# queso_dip_v4_8.net
KiCad netlist of a schematic drawn in EAGLE
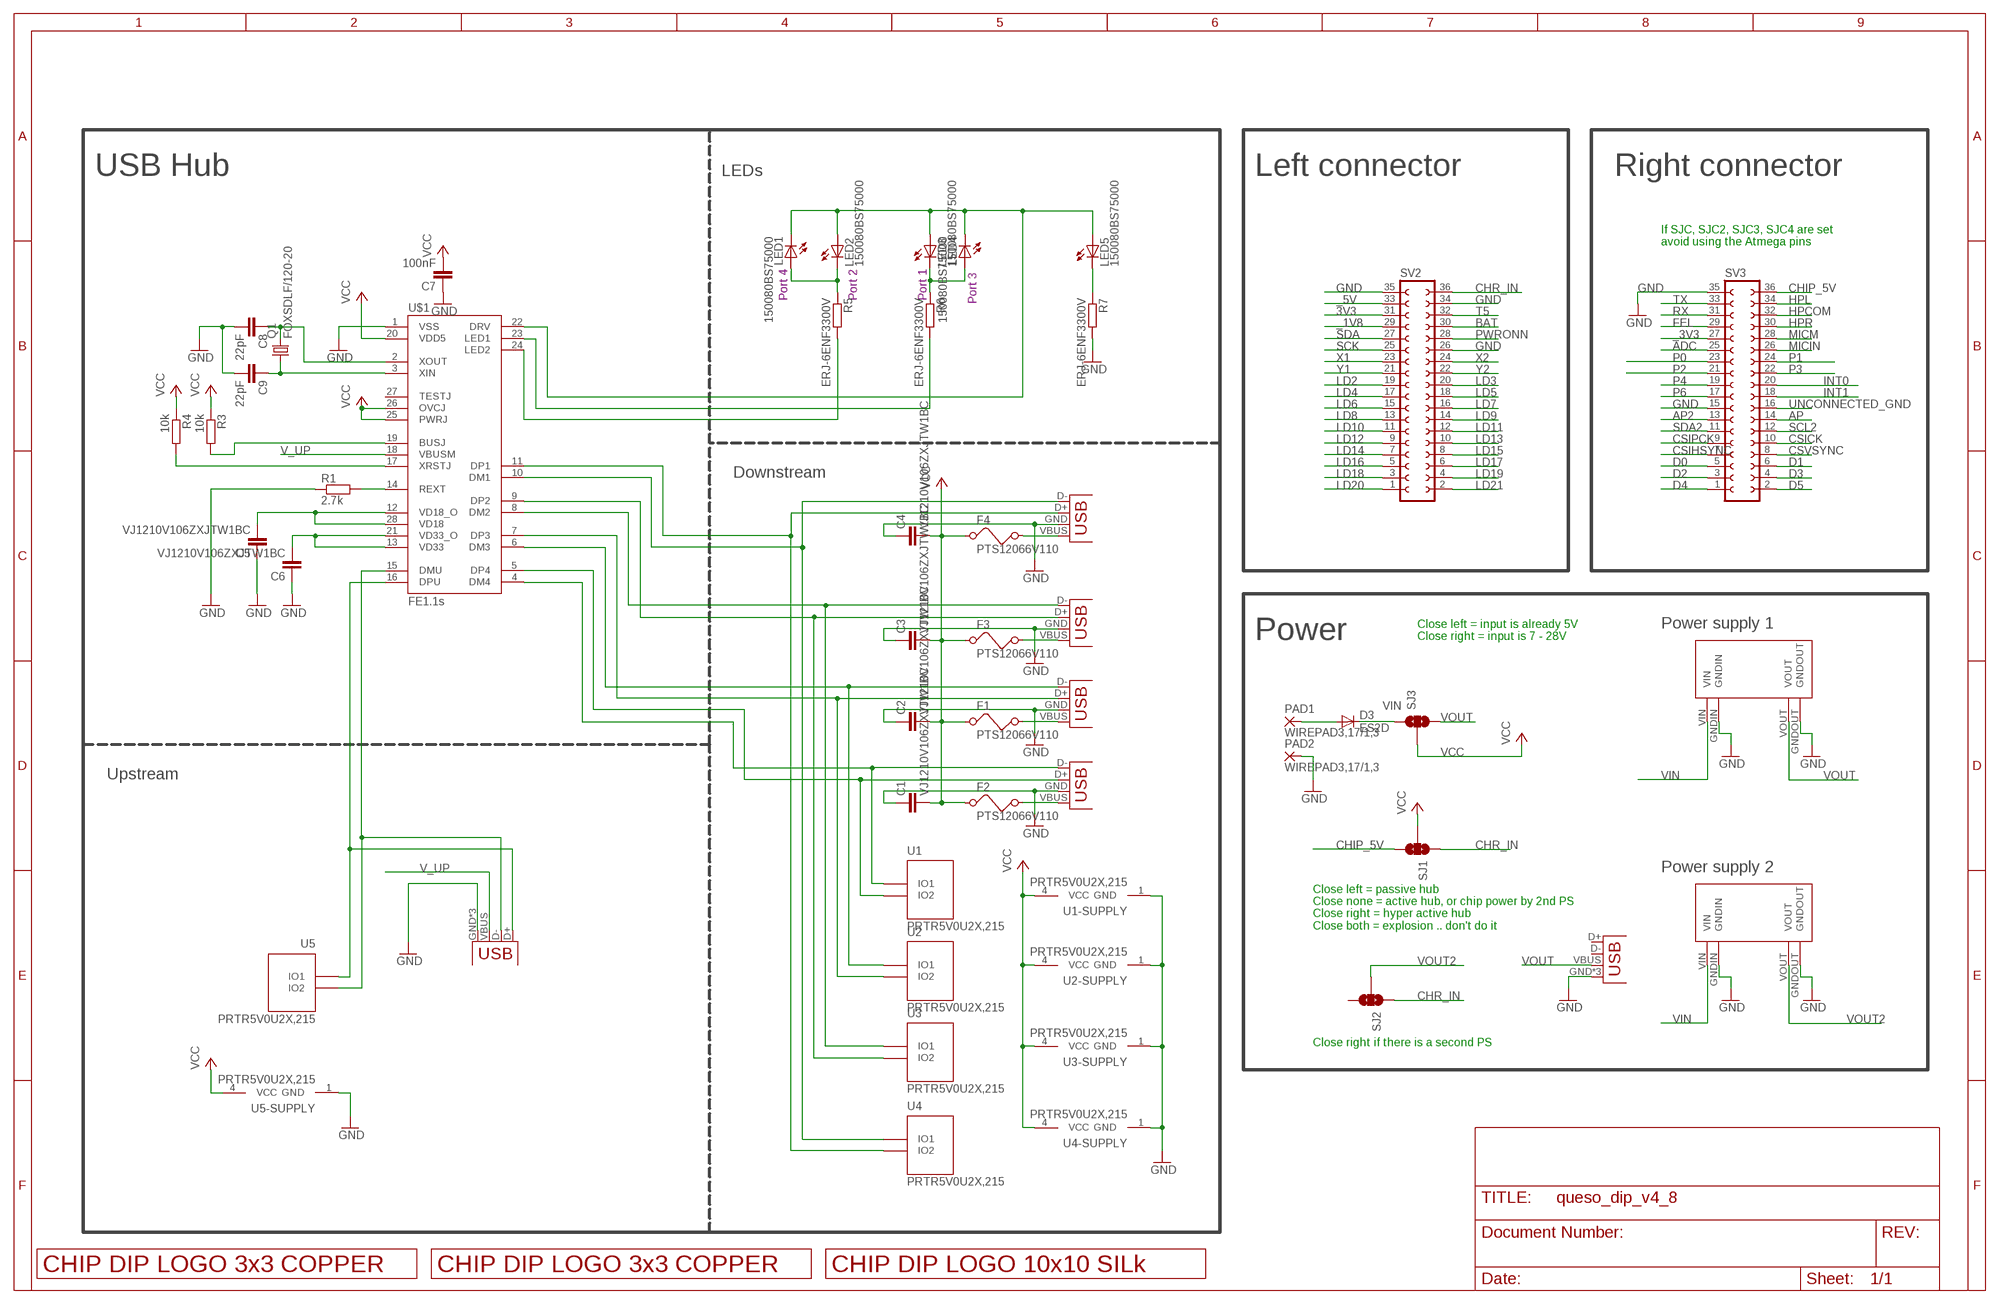
[diagram p0: schematic, sheet 1]

(export (version "E")
  (design (tool "Eeschema 10.0.6"))
  (components
    (comp (ref "C1")
      (value "VJ1210V106ZXJTW1BC")
      (footprint "eagle-import:C1210")
      (libsource (lib "eagle-import") (part "C-EUC1210"))
    )
    (comp (ref "C2")
      (value "VJ1210V106ZXJTW1BC")
      (footprint "eagle-import:C1210")
      (libsource (lib "eagle-import") (part "C-EUC1210"))
    )
    (comp (ref "C3")
      (value "VJ1210V106ZXJTW1BC")
      (footprint "eagle-import:C1210")
      (libsource (lib "eagle-import") (part "C-EUC1210"))
    )
    (comp (ref "C4")
      (value "VJ1210V106ZXJTW1BC")
      (footprint "eagle-import:C1210")
      (libsource (lib "eagle-import") (part "C-EUC1210"))
    )
    (comp (ref "C5")
      (value "VJ1210V106ZXJTW1BC")
      (footprint "eagle-import:C1210")
      (libsource (lib "eagle-import") (part "C-EUC1210"))
    )
    (comp (ref "C6")
      (value "VJ1210V106ZXJTW1BC")
      (footprint "eagle-import:C1210")
      (libsource (lib "eagle-import") (part "C-EUC1210"))
    )
    (comp (ref "C7")
      (value "100nF")
      (footprint "eagle-import:C0805")
      (libsource (lib "eagle-import") (part "C-EUC0805"))
    )
    (comp (ref "C8")
      (value "22pF")
      (footprint "eagle-import:C0805")
      (libsource (lib "eagle-import") (part "C-EUC0805"))
    )
    (comp (ref "C9")
      (value "22pF")
      (footprint "eagle-import:C0805")
      (libsource (lib "eagle-import") (part "C-EUC0805"))
    )
    (comp (ref "D3")
      (value "ES2D")
      (footprint "eagle-import:SMB")
      (libsource (lib "eagle-import") (part "ES2D"))
    )
    (comp (ref "DATA_USB")
      (value "USBUSB-MICROB-SMT-DIP")
      (footprint "eagle-import:USB-MICROB-SMT-DIP")
      (libsource (lib "eagle-import") (part "USBUSB-MICROB-SMT-DIP"))
    )
    (comp (ref "F1")
      (value "PTS12066V110")
      (footprint "eagle-import:1210")
      (libsource (lib "eagle-import") (part "FUSED"))
    )
    (comp (ref "F2")
      (value "PTS12066V110")
      (footprint "eagle-import:1210")
      (libsource (lib "eagle-import") (part "FUSED"))
    )
    (comp (ref "F3")
      (value "PTS12066V110")
      (footprint "eagle-import:1210")
      (libsource (lib "eagle-import") (part "FUSED"))
    )
    (comp (ref "F4")
      (value "PTS12066V110")
      (footprint "eagle-import:1210")
      (libsource (lib "eagle-import") (part "FUSED"))
    )
    (comp (ref "LED1")
      (value "150080BS75000")
      (footprint "eagle-import:CHIP-LED0805")
      (libsource (lib "eagle-import") (part "LEDCHIP-LED0805"))
    )
    (comp (ref "LED2")
      (value "150080BS75000")
      (footprint "eagle-import:CHIP-LED0805")
      (libsource (lib "eagle-import") (part "LEDCHIP-LED0805"))
    )
    (comp (ref "LED3")
      (value "150080BS75000")
      (footprint "eagle-import:CHIP-LED0805")
      (libsource (lib "eagle-import") (part "LEDCHIP-LED0805"))
    )
    (comp (ref "LED4")
      (value "150080BS75000")
      (footprint "eagle-import:CHIP-LED0805")
      (libsource (lib "eagle-import") (part "LEDCHIP-LED0805"))
    )
    (comp (ref "LED5")
      (value "150080BS75000")
      (footprint "eagle-import:CHIP-LED0805")
      (libsource (lib "eagle-import") (part "LEDCHIP-LED0805"))
    )
    (comp (ref "PAD1")
      (value "WIREPAD3,17/1,3")
      (footprint "eagle-import:3,17_1,3")
      (libsource (lib "eagle-import") (part "WIREPAD3,17/1,3"))
    )
    (comp (ref "PAD2")
      (value "WIREPAD3,17/1,3")
      (footprint "eagle-import:3,17_1,3")
      (libsource (lib "eagle-import") (part "WIREPAD3,17/1,3"))
    )
    (comp (ref "POWER_USB")
      (value "USBUSB-MICROB-SMT-DIP")
      (footprint "eagle-import:USB-MICROB-SMT-DIP")
      (libsource (lib "eagle-import") (part "USBUSB-MICROB-SMT-DIP"))
    )
    (comp (ref "Q1")
      (value "FOXSDLF/120-20")
      (footprint "eagle-import:SM49")
      (libsource (lib "eagle-import") (part "CRYSTALSM49"))
    )
    (comp (ref "R1")
      (value "2.7k")
      (footprint "eagle-import:R0805")
      (libsource (lib "eagle-import") (part "R-EU_R0805"))
    )
    (comp (ref "R3")
      (value "10k")
      (footprint "eagle-import:R0805")
      (libsource (lib "eagle-import") (part "R-EU_R0805"))
    )
    (comp (ref "R4")
      (value "10k")
      (footprint "eagle-import:R0805")
      (libsource (lib "eagle-import") (part "R-EU_R0805"))
    )
    (comp (ref "R5")
      (value "ERJ-6ENF3300V")
      (footprint "eagle-import:R0805")
      (libsource (lib "eagle-import") (part "R-EU_R0805"))
    )
    (comp (ref "R6")
      (value "ERJ-6ENF3300V")
      (footprint "eagle-import:R0805")
      (libsource (lib "eagle-import") (part "R-EU_R0805"))
    )
    (comp (ref "R7")
      (value "ERJ-6ENF3300V")
      (footprint "eagle-import:R0805")
      (libsource (lib "eagle-import") (part "R-EU_R0805"))
    )
    (comp (ref "SJ1")
      (value "SOLDERJUMPER_2WAYT")
      (footprint "eagle-import:SJ_2")
      (libsource (lib "eagle-import") (part "SOLDERJUMPER_2WAYT"))
    )
    (comp (ref "SJ2")
      (value "SOLDERJUMPER_2WAYT")
      (footprint "eagle-import:SJ_2")
      (libsource (lib "eagle-import") (part "SOLDERJUMPER_2WAYT"))
    )
    (comp (ref "SJ3")
      (value "SOLDERJUMPER_2WAYT")
      (footprint "eagle-import:SJ_2")
      (libsource (lib "eagle-import") (part "SOLDERJUMPER_2WAYT"))
    )
    (comp (ref "SV2")
      (value "FE18-2")
      (footprint "eagle-import:FE18-2")
      (libsource (lib "eagle-import") (part "FE18-2"))
    )
    (comp (ref "SV3")
      (value "FE18-2")
      (footprint "eagle-import:FE18-2")
      (libsource (lib "eagle-import") (part "FE18-2"))
    )
    (comp (ref "U$1")
      (value "FE1.1S")
      (footprint "eagle-import:FE1.1S_SSOP-28")
      (libsource (lib "eagle-import") (part "FE1.1S"))
    )
    (comp (ref "U$2")
      (value "LOGO_3X3_COPPER")
      (footprint "eagle-import:LOGO_3X3_COPPER")
      (libsource (lib "eagle-import") (part "LOGO_3X3_COPPER"))
    )
    (comp (ref "U$3")
      (value "MP1584EN")
      (footprint "eagle-import:MP1584EN")
      (libsource (lib "eagle-import") (part "MP1584EN"))
    )
    (comp (ref "U$4")
      (value "LOGO_3X3_COPPER")
      (footprint "eagle-import:LOGO_3X3_COPPER")
      (libsource (lib "eagle-import") (part "LOGO_3X3_COPPER"))
    )
    (comp (ref "U$5")
      (value "LOGO_10X10_SILK")
      (footprint "eagle-import:LOGO_10X10_SILK")
      (libsource (lib "eagle-import") (part "LOGO_10X10_SILK"))
    )
    (comp (ref "U$9")
      (value "MP1584EN")
      (footprint "eagle-import:MP1584EN")
      (libsource (lib "eagle-import") (part "MP1584EN"))
    )
    (comp (ref "U1")
      (value "PRTR5V0U2X,215")
      (footprint "eagle-import:SOT-143B")
      (fields (field (name "MANUFACTURER") "NXP Semiconductors"))
      (libsource (lib "eagle-import") (part "PRTR5V0U2X?"))
    )
    (comp (ref "U2")
      (value "PRTR5V0U2X,215")
      (footprint "eagle-import:SOT-143B")
      (fields (field (name "MANUFACTURER") "NXP Semiconductors"))
      (libsource (lib "eagle-import") (part "PRTR5V0U2X?"))
    )
    (comp (ref "U3")
      (value "PRTR5V0U2X,215")
      (footprint "eagle-import:SOT-143B")
      (fields (field (name "MANUFACTURER") "NXP Semiconductors"))
      (libsource (lib "eagle-import") (part "PRTR5V0U2X?"))
    )
    (comp (ref "U4")
      (value "PRTR5V0U2X,215")
      (footprint "eagle-import:SOT-143B")
      (fields (field (name "MANUFACTURER") "NXP Semiconductors"))
      (libsource (lib "eagle-import") (part "PRTR5V0U2X?"))
    )
    (comp (ref "U5")
      (value "PRTR5V0U2X,215")
      (footprint "eagle-import:SOT-143B")
      (fields (field (name "MANUFACTURER") "NXP Semiconductors"))
      (libsource (lib "eagle-import") (part "PRTR5V0U2X?"))
    )
    (comp (ref "X1")
      (value "USB-A-HU")
      (footprint "eagle-import:USB-A-HU")
      (libsource (lib "eagle-import") (part "USB-A-HU"))
    )
    (comp (ref "X2")
      (value "USB-A-HU")
      (footprint "eagle-import:USB-A-HU")
      (libsource (lib "eagle-import") (part "USB-A-HU"))
    )
    (comp (ref "X3")
      (value "USB-A-HU")
      (footprint "eagle-import:USB-A-HU")
      (libsource (lib "eagle-import") (part "USB-A-HU"))
    )
    (comp (ref "X4")
      (value "USB-A-HU")
      (footprint "eagle-import:USB-A-HU")
      (libsource (lib "eagle-import") (part "USB-A-HU"))
    )
  )
  (nets
    (net (code "1") (name "/3V3") (class "Default")
      (node (ref "SV2") (pin "31") (pinfunction "31_31") (pintype "passive"))
    )
    (net (code "2") (name "/ADC") (class "Default")
      (node (ref "SV3") (pin "25") (pinfunction "25_25") (pintype "passive"))
    )
    (net (code "3") (name "/AP") (class "Default")
      (node (ref "SV3") (pin "14") (pinfunction "14_14") (pintype "passive"))
    )
    (net (code "4") (name "/AP2") (class "Default")
      (node (ref "SV3") (pin "13") (pinfunction "13_13") (pintype "passive"))
    )
    (net (code "5") (name "/BAT") (class "Default")
      (node (ref "SV2") (pin "30") (pinfunction "30_30") (pintype "passive"))
    )
    (net (code "6") (name "/CHIP_5V") (class "Default")
      (node (ref "SJ1") (pin "3") (pinfunction "3_3") (pintype "passive"))
      (node (ref "SV3") (pin "36") (pinfunction "36_36") (pintype "passive"))
    )
    (net (code "7") (name "/CHR_IN") (class "Default")
      (node (ref "SJ1") (pin "1") (pinfunction "1_1") (pintype "passive"))
      (node (ref "SJ2") (pin "1") (pinfunction "1_1") (pintype "passive"))
      (node (ref "SV2") (pin "36") (pinfunction "36_36") (pintype "passive"))
    )
    (net (code "8") (name "/CSICK") (class "Default")
      (node (ref "SV3") (pin "10") (pinfunction "10_10") (pintype "passive"))
    )
    (net (code "9") (name "/CSIHSYNC") (class "Default")
      (node (ref "SV3") (pin "7") (pinfunction "7_7") (pintype "passive"))
    )
    (net (code "10") (name "/CSIPCK") (class "Default")
      (node (ref "SV3") (pin "9") (pinfunction "9_9") (pintype "passive"))
    )
    (net (code "11") (name "/CSVSYNC") (class "Default")
      (node (ref "SV3") (pin "8") (pinfunction "8_8") (pintype "passive"))
    )
    (net (code "12") (name "/D0") (class "Default")
      (node (ref "SV3") (pin "5") (pinfunction "5_5") (pintype "passive"))
    )
    (net (code "13") (name "/D1") (class "Default")
      (node (ref "SV3") (pin "6") (pinfunction "6_6") (pintype "passive"))
    )
    (net (code "14") (name "/D2") (class "Default")
      (node (ref "SV3") (pin "3") (pinfunction "3_3") (pintype "passive"))
    )
    (net (code "15") (name "/D3") (class "Default")
      (node (ref "SV3") (pin "4") (pinfunction "4_4") (pintype "passive"))
    )
    (net (code "16") (name "/D4") (class "Default")
      (node (ref "SV3") (pin "1") (pinfunction "1_1") (pintype "passive"))
    )
    (net (code "17") (name "/D5") (class "Default")
      (node (ref "SV3") (pin "2") (pinfunction "2_2") (pintype "passive"))
    )
    (net (code "18") (name "/FEL") (class "Default")
      (node (ref "SV3") (pin "29") (pinfunction "29_29") (pintype "passive"))
    )
    (net (code "19") (name "/HPCOM") (class "Default")
      (node (ref "SV3") (pin "32") (pinfunction "32_32") (pintype "passive"))
    )
    (net (code "20") (name "/HPL") (class "Default")
      (node (ref "SV3") (pin "34") (pinfunction "34_34") (pintype "passive"))
    )
    (net (code "21") (name "/HPR") (class "Default")
      (node (ref "SV3") (pin "30") (pinfunction "30_30") (pintype "passive"))
    )
    (net (code "22") (name "/INT0") (class "Default")
      (node (ref "SV3") (pin "20") (pinfunction "20_20") (pintype "passive"))
    )
    (net (code "23") (name "/INT1") (class "Default")
      (node (ref "SV3") (pin "18") (pinfunction "18_18") (pintype "passive"))
    )
    (net (code "24") (name "/LD2") (class "Default")
      (node (ref "SV2") (pin "19") (pinfunction "19_19") (pintype "passive"))
    )
    (net (code "25") (name "/LD3") (class "Default")
      (node (ref "SV2") (pin "20") (pinfunction "20_20") (pintype "passive"))
    )
    (net (code "26") (name "/LD4") (class "Default")
      (node (ref "SV2") (pin "17") (pinfunction "17_17") (pintype "passive"))
    )
    (net (code "27") (name "/LD5") (class "Default")
      (node (ref "SV2") (pin "18") (pinfunction "18_18") (pintype "passive"))
    )
    (net (code "28") (name "/LD6") (class "Default")
      (node (ref "SV2") (pin "15") (pinfunction "15_15") (pintype "passive"))
    )
    (net (code "29") (name "/LD7") (class "Default")
      (node (ref "SV2") (pin "16") (pinfunction "16_16") (pintype "passive"))
    )
    (net (code "30") (name "/LD8") (class "Default")
      (node (ref "SV2") (pin "13") (pinfunction "13_13") (pintype "passive"))
    )
    (net (code "31") (name "/LD9") (class "Default")
      (node (ref "SV2") (pin "14") (pinfunction "14_14") (pintype "passive"))
    )
    (net (code "32") (name "/LD10") (class "Default")
      (node (ref "SV2") (pin "11") (pinfunction "11_11") (pintype "passive"))
    )
    (net (code "33") (name "/LD11") (class "Default")
      (node (ref "SV2") (pin "12") (pinfunction "12_12") (pintype "passive"))
    )
    (net (code "34") (name "/LD12") (class "Default")
      (node (ref "SV2") (pin "9") (pinfunction "9_9") (pintype "passive"))
    )
    (net (code "35") (name "/LD13") (class "Default")
      (node (ref "SV2") (pin "10") (pinfunction "10_10") (pintype "passive"))
    )
    (net (code "36") (name "/LD14") (class "Default")
      (node (ref "SV2") (pin "7") (pinfunction "7_7") (pintype "passive"))
    )
    (net (code "37") (name "/LD15") (class "Default")
      (node (ref "SV2") (pin "8") (pinfunction "8_8") (pintype "passive"))
    )
    (net (code "38") (name "/LD16") (class "Default")
      (node (ref "SV2") (pin "5") (pinfunction "5_5") (pintype "passive"))
    )
    (net (code "39") (name "/LD17") (class "Default")
      (node (ref "SV2") (pin "6") (pinfunction "6_6") (pintype "passive"))
    )
    (net (code "40") (name "/LD18") (class "Default")
      (node (ref "SV2") (pin "3") (pinfunction "3_3") (pintype "passive"))
    )
    (net (code "41") (name "/LD19") (class "Default")
      (node (ref "SV2") (pin "4") (pinfunction "4_4") (pintype "passive"))
    )
    (net (code "42") (name "/LD20") (class "Default")
      (node (ref "SV2") (pin "1") (pinfunction "1_1") (pintype "passive"))
    )
    (net (code "43") (name "/LD21") (class "Default")
      (node (ref "SV2") (pin "2") (pinfunction "2_2") (pintype "passive"))
    )
    (net (code "44") (name "/MICIN") (class "Default")
      (node (ref "SV3") (pin "26") (pinfunction "26_26") (pintype "passive"))
    )
    (net (code "45") (name "/MICM") (class "Default")
      (node (ref "SV3") (pin "28") (pinfunction "28_28") (pintype "passive"))
    )
    (net (code "46") (name "/P0") (class "Default")
      (node (ref "SV3") (pin "23") (pinfunction "23_23") (pintype "passive"))
    )
    (net (code "47") (name "/P1") (class "Default")
      (node (ref "SV3") (pin "24") (pinfunction "24_24") (pintype "passive"))
    )
    (net (code "48") (name "/P2") (class "Default")
      (node (ref "SV3") (pin "21") (pinfunction "21_21") (pintype "passive"))
    )
    (net (code "49") (name "/P3") (class "Default")
      (node (ref "SV3") (pin "22") (pinfunction "22_22") (pintype "passive"))
    )
    (net (code "50") (name "/P4") (class "Default")
      (node (ref "SV3") (pin "19") (pinfunction "19_19") (pintype "passive"))
    )
    (net (code "51") (name "/P6") (class "Default")
      (node (ref "SV3") (pin "17") (pinfunction "17_17") (pintype "passive"))
    )
    (net (code "52") (name "/PWRONN") (class "Default")
      (node (ref "SV2") (pin "28") (pinfunction "28_28") (pintype "passive"))
    )
    (net (code "53") (name "/RX") (class "Default")
      (node (ref "SV3") (pin "31") (pinfunction "31_31") (pintype "passive"))
    )
    (net (code "54") (name "/SCK") (class "Default")
      (node (ref "SV2") (pin "25") (pinfunction "25_25") (pintype "passive"))
    )
    (net (code "55") (name "/SCL2") (class "Default")
      (node (ref "SV3") (pin "12") (pinfunction "12_12") (pintype "passive"))
    )
    (net (code "56") (name "/SDA") (class "Default")
      (node (ref "SV2") (pin "27") (pinfunction "27_27") (pintype "passive"))
    )
    (net (code "57") (name "/SDA2") (class "Default")
      (node (ref "SV3") (pin "11") (pinfunction "11_11") (pintype "passive"))
    )
    (net (code "58") (name "/T5") (class "Default")
      (node (ref "SV2") (pin "32") (pinfunction "32_32") (pintype "passive"))
    )
    (net (code "59") (name "/TX") (class "Default")
      (node (ref "SV3") (pin "33") (pinfunction "33_33") (pintype "passive"))
    )
    (net (code "60") (name "/UNCONNECTED_GND") (class "Default")
      (node (ref "SV3") (pin "16") (pinfunction "16_16") (pintype "passive"))
    )
    (net (code "61") (name "/VIN") (class "Default")
      (node (ref "D3") (pin "C") (pinfunction "C_C") (pintype "passive"))
      (node (ref "SJ3") (pin "1") (pinfunction "1_1") (pintype "passive"))
      (node (ref "U$3") (pin "VIN") (pinfunction "VIN_VIN") (pintype "power_in"))
      (node (ref "U$9") (pin "VIN") (pinfunction "VIN_VIN") (pintype "power_in"))
    )
    (net (code "62") (name "/VOUT") (class "Default")
      (node (ref "POWER_USB") (pin "VBUS") (pinfunction "VBUS_VBUS") (pintype "bidirectional"))
      (node (ref "SJ3") (pin "3") (pinfunction "3_3") (pintype "passive"))
      (node (ref "U$9") (pin "VOUT") (pinfunction "VOUT_VOUT") (pintype "power_in"))
    )
    (net (code "63") (name "/VOUT2") (class "Default")
      (node (ref "SJ2") (pin "2") (pinfunction "2_2") (pintype "passive"))
      (node (ref "U$3") (pin "VOUT") (pinfunction "VOUT_VOUT") (pintype "power_in"))
    )
    (net (code "64") (name "/V_UP") (class "Default")
      (node (ref "DATA_USB") (pin "VBUS") (pinfunction "VBUS_VBUS") (pintype "bidirectional"))
      (node (ref "U$1") (pin "18") (pinfunction "VBUSM_18") (pintype "bidirectional"))
    )
    (net (code "65") (name "/X1") (class "Default")
      (node (ref "SV2") (pin "23") (pinfunction "23_23") (pintype "passive"))
    )
    (net (code "66") (name "/X2") (class "Default")
      (node (ref "SV2") (pin "24") (pinfunction "24_24") (pintype "passive"))
    )
    (net (code "67") (name "/Y1") (class "Default")
      (node (ref "SV2") (pin "21") (pinfunction "21_21") (pintype "passive"))
    )
    (net (code "68") (name "/Y2") (class "Default")
      (node (ref "SV2") (pin "22") (pinfunction "22_22") (pintype "passive"))
    )
    (net (code "69") (name "/_1V8") (class "Default")
      (node (ref "SV2") (pin "29") (pinfunction "29_29") (pintype "passive"))
    )
    (net (code "70") (name "/_3V3") (class "Default")
      (node (ref "SV3") (pin "27") (pinfunction "27_27") (pintype "passive"))
    )
    (net (code "71") (name "/_5V") (class "Default")
      (node (ref "SV2") (pin "33") (pinfunction "33_33") (pintype "passive"))
    )
    (net (code "72") (name "GND") (class "Default")
      (node (ref "C1") (pin "1") (pinfunction "1_1") (pintype "passive"))
      (node (ref "C2") (pin "1") (pinfunction "1_1") (pintype "passive"))
      (node (ref "C3") (pin "1") (pinfunction "1_1") (pintype "passive"))
      (node (ref "C4") (pin "1") (pinfunction "1_1") (pintype "passive"))
      (node (ref "C5") (pin "1") (pinfunction "1_1") (pintype "passive"))
      (node (ref "C6") (pin "1") (pinfunction "1_1") (pintype "passive"))
      (node (ref "C7") (pin "1") (pinfunction "1_1") (pintype "passive"))
      (node (ref "C8") (pin "2") (pinfunction "2_2") (pintype "passive"))
      (node (ref "C9") (pin "2") (pinfunction "2_2") (pintype "passive"))
      (node (ref "DATA_USB") (pin "GND") (pinfunction "GND_GND") (pintype "bidirectional"))
      (node (ref "DATA_USB") (pin "MT1") (pinfunction "GND_MT1") (pintype "bidirectional"))
      (node (ref "DATA_USB") (pin "MT2") (pinfunction "GND_MT2") (pintype "bidirectional"))
      (node (ref "PAD2") (pin "1") (pinfunction "P_1") (pintype "passive"))
      (node (ref "POWER_USB") (pin "GND") (pinfunction "GND_GND") (pintype "bidirectional"))
      (node (ref "POWER_USB") (pin "MT1") (pinfunction "GND_MT1") (pintype "bidirectional"))
      (node (ref "POWER_USB") (pin "MT2") (pinfunction "GND_MT2") (pintype "bidirectional"))
      (node (ref "R1") (pin "1") (pinfunction "1_1") (pintype "passive"))
      (node (ref "R7") (pin "2") (pinfunction "2_2") (pintype "passive"))
      (node (ref "SV2") (pin "26") (pinfunction "26_26") (pintype "passive"))
      (node (ref "SV2") (pin "34") (pinfunction "34_34") (pintype "passive"))
      (node (ref "SV2") (pin "35") (pinfunction "35_35") (pintype "passive"))
      (node (ref "SV3") (pin "15") (pinfunction "15_15") (pintype "passive"))
      (node (ref "SV3") (pin "35") (pinfunction "35_35") (pintype "passive"))
      (node (ref "U$1") (pin "1") (pinfunction "VSS_1") (pintype "bidirectional"))
      (node (ref "U$3") (pin "GNDIN") (pinfunction "GNDIN_GNDIN") (pintype "power_in"))
      (node (ref "U$3") (pin "GNDOUT") (pinfunction "GNDOUT_GNDOUT") (pintype "power_in"))
      (node (ref "U$9") (pin "GNDIN") (pinfunction "GNDIN_GNDIN") (pintype "power_in"))
      (node (ref "U$9") (pin "GNDOUT") (pinfunction "GNDOUT_GNDOUT") (pintype "power_in"))
      (node (ref "U1") (pin "1") (pinfunction "GND_1") (pintype "bidirectional"))
      (node (ref "U2") (pin "1") (pinfunction "GND_1") (pintype "bidirectional"))
      (node (ref "U3") (pin "1") (pinfunction "GND_1") (pintype "bidirectional"))
      (node (ref "U4") (pin "1") (pinfunction "GND_1") (pintype "bidirectional"))
      (node (ref "U5") (pin "1") (pinfunction "GND_1") (pintype "bidirectional"))
      (node (ref "X1") (pin "GND") (pinfunction "VBUS_GND") (pintype "bidirectional"))
      (node (ref "X2") (pin "GND") (pinfunction "VBUS_GND") (pintype "bidirectional"))
      (node (ref "X3") (pin "GND") (pinfunction "VBUS_GND") (pintype "bidirectional"))
      (node (ref "X4") (pin "GND") (pinfunction "VBUS_GND") (pintype "bidirectional"))
    )
    (net (code "73") (name "Net-(LED1-PadA)") (class "Default")
      (node (ref "LED1") (pin "A") (pinfunction "A_A") (pintype "passive"))
      (node (ref "LED2") (pin "C") (pinfunction "C_C") (pintype "passive"))
      (node (ref "R5") (pin "1") (pinfunction "1_1") (pintype "passive"))
    )
    (net (code "74") (name "Net-(LED3-PadC)") (class "Default")
      (node (ref "LED3") (pin "C") (pinfunction "C_C") (pintype "passive"))
      (node (ref "LED4") (pin "A") (pinfunction "A_A") (pintype "passive"))
      (node (ref "R6") (pin "1") (pinfunction "1_1") (pintype "passive"))
    )
    (net (code "75") (name "Net-(LED5-PadC)") (class "Default")
      (node (ref "LED5") (pin "C") (pinfunction "C_C") (pintype "passive"))
      (node (ref "R7") (pin "1") (pinfunction "1_1") (pintype "passive"))
    )
    (net (code "76") (name "Net-(PAD1-P)") (class "Default")
      (node (ref "D3") (pin "A") (pinfunction "A_A") (pintype "passive"))
      (node (ref "PAD1") (pin "1") (pinfunction "P_1") (pintype "passive"))
    )
    (net (code "77") (name "Net-(U$1-BUSJ)") (class "Default")
      (node (ref "R3") (pin "2") (pinfunction "2_2") (pintype "passive"))
      (node (ref "U$1") (pin "19") (pinfunction "BUSJ_19") (pintype "bidirectional"))
    )
    (net (code "78") (name "Net-(U$1-DM1)") (class "Default")
      (node (ref "U$1") (pin "10") (pinfunction "DM1_10") (pintype "bidirectional"))
      (node (ref "U4") (pin "2") (pinfunction "IO1_2") (pintype "bidirectional"))
      (node (ref "X4") (pin "D-") (pinfunction "D+_D-") (pintype "bidirectional"))
    )
    (net (code "79") (name "Net-(U$1-DM2)") (class "Default")
      (node (ref "U$1") (pin "8") (pinfunction "DM2_8") (pintype "bidirectional"))
      (node (ref "U3") (pin "2") (pinfunction "IO1_2") (pintype "bidirectional"))
      (node (ref "X3") (pin "D-") (pinfunction "D+_D-") (pintype "bidirectional"))
    )
    (net (code "80") (name "Net-(U$1-DM3)") (class "Default")
      (node (ref "U$1") (pin "6") (pinfunction "DM3_6") (pintype "bidirectional"))
      (node (ref "U2") (pin "2") (pinfunction "IO1_2") (pintype "bidirectional"))
      (node (ref "X2") (pin "D-") (pinfunction "D+_D-") (pintype "bidirectional"))
    )
    (net (code "81") (name "Net-(U$1-DM4)") (class "Default")
      (node (ref "U$1") (pin "4") (pinfunction "DM4_4") (pintype "bidirectional"))
      (node (ref "U1") (pin "2") (pinfunction "IO1_2") (pintype "bidirectional"))
      (node (ref "X1") (pin "D-") (pinfunction "D+_D-") (pintype "bidirectional"))
    )
    (net (code "82") (name "Net-(U$1-DMU)") (class "Default")
      (node (ref "DATA_USB") (pin "D-") (pinfunction "D-_D-") (pintype "bidirectional"))
      (node (ref "U$1") (pin "15") (pinfunction "DMU_15") (pintype "bidirectional"))
      (node (ref "U5") (pin "3") (pinfunction "IO2_3") (pintype "bidirectional"))
    )
    (net (code "83") (name "Net-(U$1-DP1)") (class "Default")
      (node (ref "U$1") (pin "11") (pinfunction "DP1_11") (pintype "bidirectional"))
      (node (ref "U4") (pin "3") (pinfunction "IO2_3") (pintype "bidirectional"))
      (node (ref "X4") (pin "D+") (pinfunction "D-_D+") (pintype "bidirectional"))
    )
    (net (code "84") (name "Net-(U$1-DP2)") (class "Default")
      (node (ref "U$1") (pin "9") (pinfunction "DP2_9") (pintype "bidirectional"))
      (node (ref "U3") (pin "3") (pinfunction "IO2_3") (pintype "bidirectional"))
      (node (ref "X3") (pin "D+") (pinfunction "D-_D+") (pintype "bidirectional"))
    )
    (net (code "85") (name "Net-(U$1-DP3)") (class "Default")
      (node (ref "U$1") (pin "7") (pinfunction "DP3_7") (pintype "bidirectional"))
      (node (ref "U2") (pin "3") (pinfunction "IO2_3") (pintype "bidirectional"))
      (node (ref "X2") (pin "D+") (pinfunction "D-_D+") (pintype "bidirectional"))
    )
    (net (code "86") (name "Net-(U$1-DP4)") (class "Default")
      (node (ref "U$1") (pin "5") (pinfunction "DP4_5") (pintype "bidirectional"))
      (node (ref "U1") (pin "3") (pinfunction "IO2_3") (pintype "bidirectional"))
      (node (ref "X1") (pin "D+") (pinfunction "D-_D+") (pintype "bidirectional"))
    )
    (net (code "87") (name "Net-(U$1-DPU)") (class "Default")
      (node (ref "DATA_USB") (pin "D+") (pinfunction "D+_D+") (pintype "bidirectional"))
      (node (ref "U$1") (pin "16") (pinfunction "DPU_16") (pintype "bidirectional"))
      (node (ref "U5") (pin "2") (pinfunction "IO1_2") (pintype "bidirectional"))
    )
    (net (code "88") (name "Net-(U$1-DRV)") (class "Default")
      (node (ref "LED1") (pin "C") (pinfunction "C_C") (pintype "passive"))
      (node (ref "LED2") (pin "A") (pinfunction "A_A") (pintype "passive"))
      (node (ref "LED3") (pin "A") (pinfunction "A_A") (pintype "passive"))
      (node (ref "LED4") (pin "C") (pinfunction "C_C") (pintype "passive"))
      (node (ref "LED5") (pin "A") (pinfunction "A_A") (pintype "passive"))
      (node (ref "U$1") (pin "22") (pinfunction "DRV_22") (pintype "bidirectional"))
    )
    (net (code "89") (name "Net-(U$1-LED1)") (class "Default")
      (node (ref "R6") (pin "2") (pinfunction "2_2") (pintype "passive"))
      (node (ref "U$1") (pin "23") (pinfunction "LED1_23") (pintype "bidirectional"))
    )
    (net (code "90") (name "Net-(U$1-LED2)") (class "Default")
      (node (ref "R5") (pin "2") (pinfunction "2_2") (pintype "passive"))
      (node (ref "U$1") (pin "24") (pinfunction "LED2_24") (pintype "bidirectional"))
    )
    (net (code "91") (name "Net-(U$1-REXT)") (class "Default")
      (node (ref "R1") (pin "2") (pinfunction "2_2") (pintype "passive"))
      (node (ref "U$1") (pin "14") (pinfunction "REXT_14") (pintype "bidirectional"))
    )
    (net (code "92") (name "Net-(U$1-VD18)") (class "Default")
      (node (ref "C5") (pin "2") (pinfunction "2_2") (pintype "passive"))
      (node (ref "U$1") (pin "12") (pinfunction "VD18_O_12") (pintype "bidirectional"))
      (node (ref "U$1") (pin "28") (pinfunction "VD18_28") (pintype "bidirectional"))
    )
    (net (code "93") (name "Net-(U$1-VD33)") (class "Default")
      (node (ref "C6") (pin "2") (pinfunction "2_2") (pintype "passive"))
      (node (ref "U$1") (pin "13") (pinfunction "VD33_13") (pintype "bidirectional"))
      (node (ref "U$1") (pin "21") (pinfunction "VD33_O_21") (pintype "bidirectional"))
    )
    (net (code "94") (name "Net-(U$1-XIN)") (class "Default")
      (node (ref "C9") (pin "1") (pinfunction "1_1") (pintype "passive"))
      (node (ref "Q1") (pin "1") (pinfunction "1_1") (pintype "passive"))
      (node (ref "U$1") (pin "3") (pinfunction "XIN_3") (pintype "bidirectional"))
    )
    (net (code "95") (name "Net-(U$1-XOUT)") (class "Default")
      (node (ref "C8") (pin "1") (pinfunction "1_1") (pintype "passive"))
      (node (ref "Q1") (pin "2") (pinfunction "2_2") (pintype "passive"))
      (node (ref "U$1") (pin "2") (pinfunction "XOUT_2") (pintype "bidirectional"))
    )
    (net (code "96") (name "Net-(U$1-XRSTJ)") (class "Default")
      (node (ref "R4") (pin "2") (pinfunction "2_2") (pintype "passive"))
      (node (ref "U$1") (pin "17") (pinfunction "XRSTJ_17") (pintype "bidirectional"))
    )
    (net (code "97") (name "Net-(X1-GND)") (class "Default")
      (node (ref "F2") (pin "2") (pinfunction "2_2") (pintype "passive"))
      (node (ref "X1") (pin "VBUS") (pinfunction "GND_VBUS") (pintype "bidirectional"))
    )
    (net (code "98") (name "Net-(X2-GND)") (class "Default")
      (node (ref "F1") (pin "2") (pinfunction "2_2") (pintype "passive"))
      (node (ref "X2") (pin "VBUS") (pinfunction "GND_VBUS") (pintype "bidirectional"))
    )
    (net (code "99") (name "Net-(X3-GND)") (class "Default")
      (node (ref "F3") (pin "2") (pinfunction "2_2") (pintype "passive"))
      (node (ref "X3") (pin "VBUS") (pinfunction "GND_VBUS") (pintype "bidirectional"))
    )
    (net (code "100") (name "Net-(X4-GND)") (class "Default")
      (node (ref "F4") (pin "2") (pinfunction "2_2") (pintype "passive"))
      (node (ref "X4") (pin "VBUS") (pinfunction "GND_VBUS") (pintype "bidirectional"))
    )
    (net (code "101") (name "VCC") (class "Default")
      (node (ref "C1") (pin "2") (pinfunction "2_2") (pintype "passive"))
      (node (ref "C2") (pin "2") (pinfunction "2_2") (pintype "passive"))
      (node (ref "C3") (pin "2") (pinfunction "2_2") (pintype "passive"))
      (node (ref "C4") (pin "2") (pinfunction "2_2") (pintype "passive"))
      (node (ref "C7") (pin "2") (pinfunction "2_2") (pintype "passive"))
      (node (ref "F1") (pin "1") (pinfunction "1_1") (pintype "passive"))
      (node (ref "F2") (pin "1") (pinfunction "1_1") (pintype "passive"))
      (node (ref "F3") (pin "1") (pinfunction "1_1") (pintype "passive"))
      (node (ref "F4") (pin "1") (pinfunction "1_1") (pintype "passive"))
      (node (ref "R3") (pin "1") (pinfunction "1_1") (pintype "passive"))
      (node (ref "R4") (pin "1") (pinfunction "1_1") (pintype "passive"))
      (node (ref "SJ1") (pin "2") (pinfunction "2_2") (pintype "passive"))
      (node (ref "SJ3") (pin "2") (pinfunction "2_2") (pintype "passive"))
      (node (ref "U$1") (pin "20") (pinfunction "VDD5_20") (pintype "bidirectional"))
      (node (ref "U$1") (pin "25") (pinfunction "PWRJ_25") (pintype "bidirectional"))
      (node (ref "U$1") (pin "26") (pinfunction "OVCJ_26") (pintype "bidirectional"))
      (node (ref "U1") (pin "4") (pinfunction "VCC_4") (pintype "bidirectional"))
      (node (ref "U2") (pin "4") (pinfunction "VCC_4") (pintype "bidirectional"))
      (node (ref "U3") (pin "4") (pinfunction "VCC_4") (pintype "bidirectional"))
      (node (ref "U4") (pin "4") (pinfunction "VCC_4") (pintype "bidirectional"))
      (node (ref "U5") (pin "4") (pinfunction "VCC_4") (pintype "bidirectional"))
    )
    (net (code "102") (name "unconnected-(POWER_USB-PadD+)") (class "Default")
      (node (ref "POWER_USB") (pin "D+") (pinfunction "D+_D+") (pintype "bidirectional"))
    )
    (net (code "103") (name "unconnected-(POWER_USB-PadD-)") (class "Default")
      (node (ref "POWER_USB") (pin "D-") (pinfunction "D-_D-") (pintype "bidirectional"))
    )
    (net (code "104") (name "unconnected-(SJ2-Pad3)") (class "Default")
      (node (ref "SJ2") (pin "3") (pinfunction "3_3") (pintype "passive"))
    )
    (net (code "105") (name "unconnected-(U$1-TESTJ-Pad27)") (class "Default")
      (node (ref "U$1") (pin "27") (pinfunction "TESTJ_27") (pintype "bidirectional"))
    )
  )
)
